# SCH_Senior_Transmitter_2026-04-14.net
KiCad netlist of a schematic drawn in EasyEDA
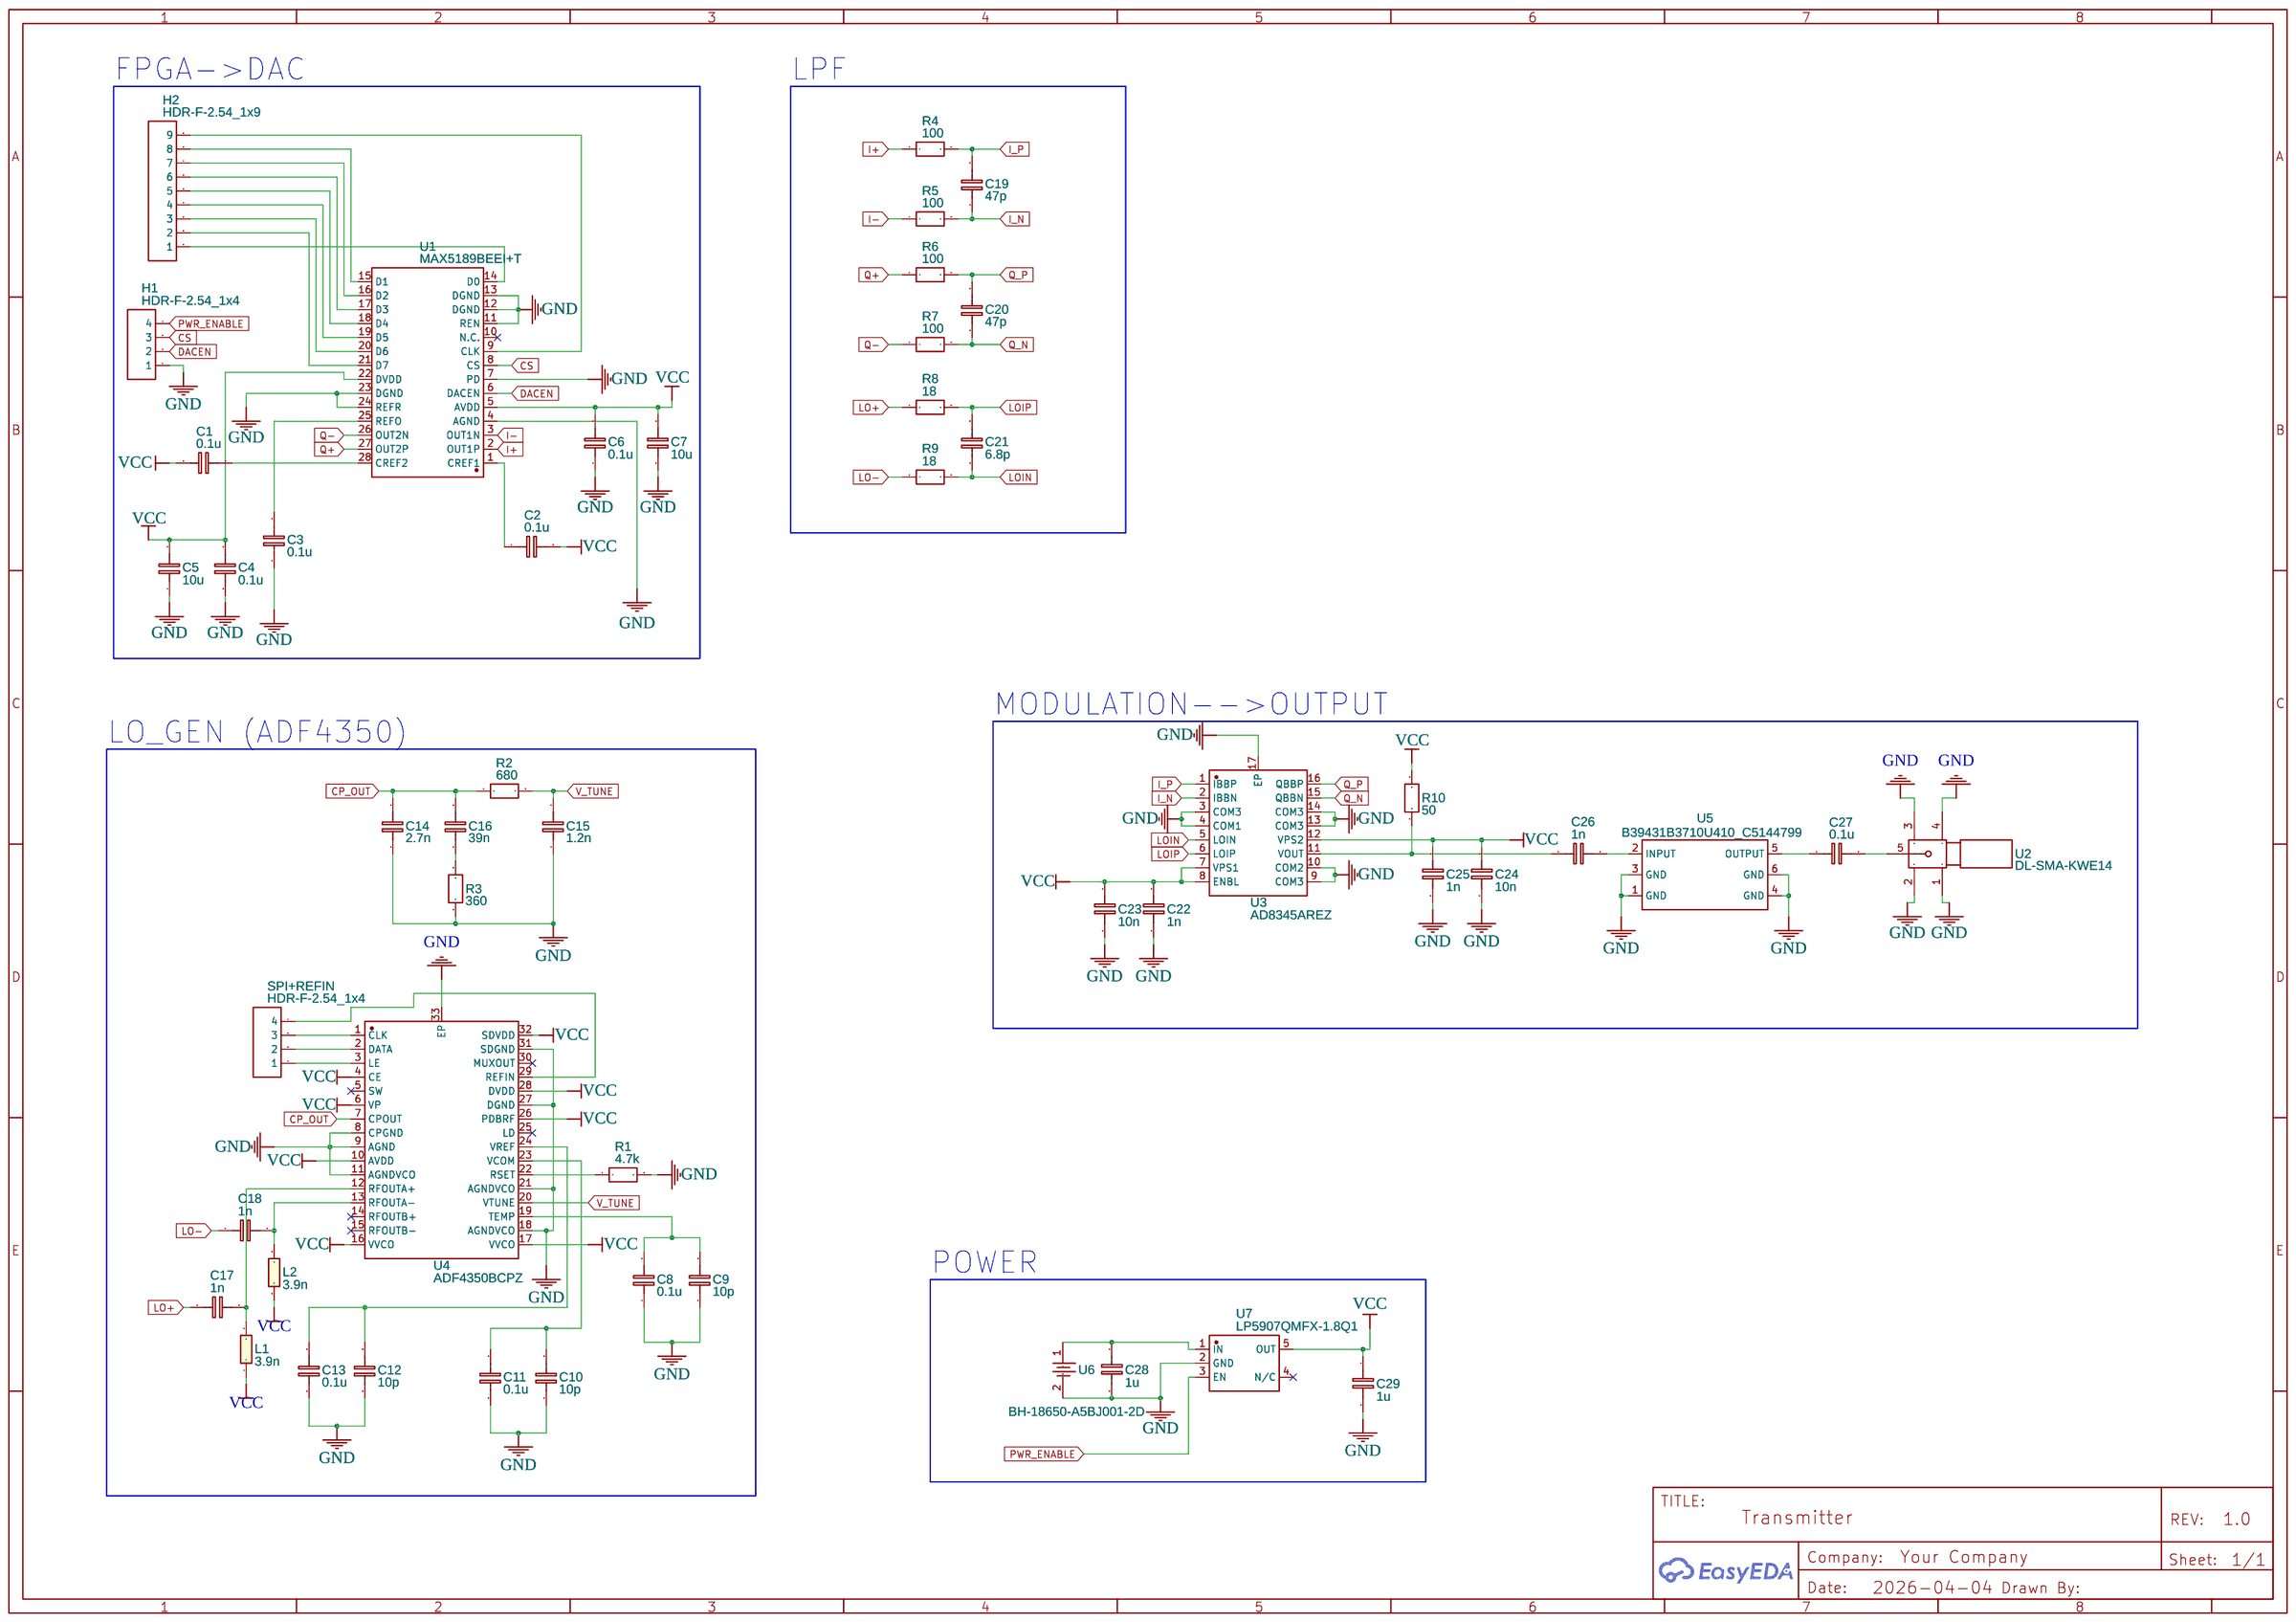
[diagram p0: schematic sheet]

(export (version "E")
  (design (tool "Eeschema 10.0.6"))
  (components
    (comp (ref "C1") (value "0.1u") (libsource (lib "") (part "C_0603_EU_6")))
    (comp (ref "C2") (value "0.1u") (libsource (lib "") (part "C_0603_EU_6")))
    (comp (ref "C3") (value "0.1u") (libsource (lib "") (part "C_0603_EU_2")))
    (comp (ref "C4") (value "0.1u") (libsource (lib "") (part "C_0603_EU_2")))
    (comp (ref "C5") (value "10u") (libsource (lib "") (part "C_0603_EU_2")))
    (comp (ref "C6") (value "0.1u") (libsource (lib "") (part "C_0603_EU_3")))
    (comp (ref "C7") (value "10u") (libsource (lib "") (part "C_0603_EU_3")))
    (comp (ref "C8") (value "0.1u") (libsource (lib "") (part "C_0603_EU_1")))
    (comp (ref "C9") (value "10p") (libsource (lib "") (part "C_0603_EU_1")))
    (comp (ref "C10") (value "10p") (libsource (lib "") (part "C_0603_EU_3")))
    (comp (ref "C11") (value "0.1u") (libsource (lib "") (part "C_0603_EU_3")))
    (comp (ref "C12") (value "10p") (libsource (lib "") (part "C_0603_EU_3")))
    (comp (ref "C13") (value "0.1u") (libsource (lib "") (part "C_0603_EU_2")))
    (comp (ref "C14") (value "2.7n") (libsource (lib "") (part "C_0603_EU_1")))
    (comp (ref "C15") (value "1.2n") (libsource (lib "") (part "C_0603_EU_1")))
    (comp (ref "C16") (value "39n") (libsource (lib "") (part "C_0603_EU_1")))
    (comp (ref "C17") (value "1n") (libsource (lib "") (part "C_0603_EU_6")))
    (comp (ref "C18") (value "1n") (libsource (lib "") (part "C_0603_EU_5")))
    (comp (ref "C19") (value "47p") (libsource (lib "") (part "C_0603_EU_2")))
    (comp (ref "C20") (value "47p") (libsource (lib "") (part "C_0603_EU_2")))
    (comp (ref "C21") (value "6.8p") (libsource (lib "") (part "C_0402_EU")))
    (comp (ref "C22") (value "1n") (libsource (lib "") (part "C_0603_EU")))
    (comp (ref "C23") (value "10n") (libsource (lib "") (part "C_0603_EU")))
    (comp (ref "C24") (value "10n") (libsource (lib "") (part "C_0603_EU")))
    (comp (ref "C25") (value "1n") (libsource (lib "") (part "C_0603_EU")))
    (comp (ref "C26") (value "1n") (libsource (lib "") (part "C_0603_EU_4")))
    (comp (ref "C27") (value "0.1u") (libsource (lib "") (part "C_0603_EU_4")))
    (comp (ref "C28") (value "1u") (libsource (lib "") (part "C_0603_EU_7")))
    (comp (ref "C29") (value "1u") (libsource (lib "") (part "C_0603_EU_7")))
    (comp (ref "H1") (value "HDR-F-2.54_1x4") (libsource (lib "") (part "HDR-F-2.54_1x4")))
    (comp (ref "H2") (value "HDR-F-2.54_1x9") (libsource (lib "") (part "HDR-F-2.54_1x9")))
    (comp (ref "L1") (value "3.9n") (libsource (lib "") (part "L0603_EU")))
    (comp (ref "L2") (value "3.9n") (libsource (lib "") (part "L0603_EU")))
    (comp (ref "R1") (value "4.7k") (libsource (lib "") (part "R_0603_EU")))
    (comp (ref "R2") (value "680") (libsource (lib "") (part "R_0603_EU")))
    (comp (ref "R3") (value "360") (libsource (lib "") (part "R_0603_EU_1")))
    (comp (ref "R4") (value "100") (libsource (lib "") (part "R_0603_EU")))
    (comp (ref "R5") (value "100") (libsource (lib "") (part "R_0603_EU")))
    (comp (ref "R6") (value "100") (libsource (lib "") (part "R_0603_EU")))
    (comp (ref "R7") (value "100") (libsource (lib "") (part "R_0603_EU")))
    (comp (ref "R8") (value "18") (libsource (lib "") (part "R_0402_EU")))
    (comp (ref "R9") (value "18") (libsource (lib "") (part "R_0402_EU")))
    (comp (ref "R10") (value "50") (libsource (lib "") (part "R_0603_EU_1")))
    (comp (ref "SPI+REFIN") (value "HDR-F-2.54_1x4") (libsource (lib "") (part "HDR-F-2.54_1x4_1")))
    (comp (ref "U1")
      (value "MAX5189BEEI+T")
      (fields (field (name "Manufacturer") "ADI(亚德诺)/MAXIM(美信)"))
      (libsource (lib "") (part "MAX5189BEEI+T"))
    )
    (comp (ref "U2")
      (value "DL-SMA-KWE14")
      (fields (field (name "Manufacturer") "DEALON(德艺隆)"))
      (libsource (lib "") (part "DL-SMA-KWE14"))
    )
    (comp (ref "U3")
      (value "AD8345AREZ")
      (fields (field (name "Manufacturer") "ADI(亚德诺)"))
      (libsource (lib "") (part "AD8345AREZ"))
    )
    (comp (ref "U4")
      (value "ADF4350BCPZ")
      (fields (field (name "Manufacturer") "ADI(亚德诺)"))
      (libsource (lib "") (part "ADF4350BCPZ"))
    )
    (comp (ref "U5")
      (value "B39431B3710U410_C5144799")
      (fields (field (name "Manufacturer Part") "B39431B3710U410"))
      (libsource (lib "") (part "B39431B3710U410_C5144799"))
    )
    (comp (ref "U6")
      (value "BH-18650-A5BJ001-2D")
      (fields (field (name "Manufacturer") "MYOUNG(美阳)"))
      (libsource (lib "") (part "BH-18650-A5BJ001-2D"))
    )
    (comp (ref "U7")
      (value "LP5907QMFX-1.8Q1")
      (fields (field (name "Manufacturer") "TI(德州仪器)"))
      (libsource (lib "") (part "LP5907QMFX-1.8Q1"))
    )
  )
  (nets
    (net (code "1") (name "CP_OUT") (class "Default")
      (node (ref "C14") (pin "2") (pinfunction "2_2") (pintype "unspecified"))
      (node (ref "C16") (pin "2") (pinfunction "2_2") (pintype "unspecified"))
      (node (ref "R2") (pin "1") (pinfunction "1_1") (pintype "unspecified"))
      (node (ref "U4") (pin "7") (pinfunction "CPOUT_7") (pintype "unspecified"))
    )
    (net (code "2") (name "CS") (class "Default")
      (node (ref "H1") (pin "3") (pinfunction "3_3") (pintype "unspecified"))
      (node (ref "U1") (pin "8") (pinfunction "CS_8") (pintype "unspecified"))
    )
    (net (code "3") (name "DACEN") (class "Default")
      (node (ref "H1") (pin "2") (pinfunction "2_2") (pintype "unspecified"))
      (node (ref "U1") (pin "6") (pinfunction "DACEN_6") (pintype "unspecified"))
    )
    (net (code "4") (name "GND") (class "Default")
      (node (ref "C10") (pin "1") (pinfunction "1_1") (pintype "unspecified"))
      (node (ref "C11") (pin "1") (pinfunction "1_1") (pintype "unspecified"))
      (node (ref "C12") (pin "1") (pinfunction "1_1") (pintype "unspecified"))
      (node (ref "C13") (pin "1") (pinfunction "1_1") (pintype "unspecified"))
      (node (ref "C14") (pin "1") (pinfunction "1_1") (pintype "unspecified"))
      (node (ref "C15") (pin "1") (pinfunction "1_1") (pintype "unspecified"))
      (node (ref "C22") (pin "2") (pinfunction "2_2") (pintype "unspecified"))
      (node (ref "C23") (pin "2") (pinfunction "2_2") (pintype "unspecified"))
      (node (ref "C24") (pin "2") (pinfunction "2_2") (pintype "unspecified"))
      (node (ref "C25") (pin "2") (pinfunction "2_2") (pintype "unspecified"))
      (node (ref "C28") (pin "2") (pinfunction "2_2") (pintype "unspecified"))
      (node (ref "C29") (pin "2") (pinfunction "2_2") (pintype "unspecified"))
      (node (ref "C3") (pin "1") (pinfunction "1_1") (pintype "unspecified"))
      (node (ref "C4") (pin "1") (pinfunction "1_1") (pintype "unspecified"))
      (node (ref "C5") (pin "1") (pinfunction "1_1") (pintype "unspecified"))
      (node (ref "C6") (pin "1") (pinfunction "1_1") (pintype "unspecified"))
      (node (ref "C7") (pin "1") (pinfunction "1_1") (pintype "unspecified"))
      (node (ref "C8") (pin "1") (pinfunction "1_1") (pintype "unspecified"))
      (node (ref "C9") (pin "1") (pinfunction "1_1") (pintype "unspecified"))
      (node (ref "H1") (pin "1") (pinfunction "1_1") (pintype "unspecified"))
      (node (ref "R1") (pin "2") (pinfunction "2_2") (pintype "unspecified"))
      (node (ref "R3") (pin "1") (pinfunction "1_1") (pintype "unspecified"))
      (node (ref "U1") (pin "11") (pinfunction "REN_11") (pintype "unspecified"))
      (node (ref "U1") (pin "12") (pinfunction "DGND_12") (pintype "unspecified"))
      (node (ref "U1") (pin "13") (pinfunction "DGND_13") (pintype "unspecified"))
      (node (ref "U1") (pin "23") (pinfunction "DGND_23") (pintype "unspecified"))
      (node (ref "U1") (pin "24") (pinfunction "REFR_24") (pintype "unspecified"))
      (node (ref "U1") (pin "4") (pinfunction "AGND_4") (pintype "unspecified"))
      (node (ref "U1") (pin "7") (pinfunction "PD_7") (pintype "unspecified"))
      (node (ref "U2") (pin "1") (pinfunction "1_1") (pintype "unspecified"))
      (node (ref "U2") (pin "2") (pinfunction "2_2") (pintype "unspecified"))
      (node (ref "U2") (pin "3") (pinfunction "3_3") (pintype "unspecified"))
      (node (ref "U2") (pin "4") (pinfunction "4_4") (pintype "unspecified"))
      (node (ref "U3") (pin "10") (pinfunction "COM2_10") (pintype "unspecified"))
      (node (ref "U3") (pin "13") (pinfunction "COM3_13") (pintype "unspecified"))
      (node (ref "U3") (pin "14") (pinfunction "COM3_14") (pintype "unspecified"))
      (node (ref "U3") (pin "17") (pinfunction "EP_17") (pintype "unspecified"))
      (node (ref "U3") (pin "3") (pinfunction "COM3_3") (pintype "unspecified"))
      (node (ref "U3") (pin "4") (pinfunction "COM1_4") (pintype "unspecified"))
      (node (ref "U3") (pin "9") (pinfunction "COM3_9") (pintype "unspecified"))
      (node (ref "U4") (pin "11") (pinfunction "AGNDVCO_11") (pintype "unspecified"))
      (node (ref "U4") (pin "18") (pinfunction "AGNDVCO_18") (pintype "unspecified"))
      (node (ref "U4") (pin "21") (pinfunction "AGNDVCO_21") (pintype "unspecified"))
      (node (ref "U4") (pin "27") (pinfunction "DGND_27") (pintype "unspecified"))
      (node (ref "U4") (pin "31") (pinfunction "SDGND_31") (pintype "unspecified"))
      (node (ref "U4") (pin "33") (pinfunction "EP_33") (pintype "unspecified"))
      (node (ref "U4") (pin "8") (pinfunction "CPGND_8") (pintype "unspecified"))
      (node (ref "U4") (pin "9") (pinfunction "AGND_9") (pintype "unspecified"))
      (node (ref "U5") (pin "1") (pinfunction "GND_1") (pintype "unspecified"))
      (node (ref "U5") (pin "3") (pinfunction "GND_3") (pintype "unspecified"))
      (node (ref "U5") (pin "4") (pinfunction "GND_4") (pintype "unspecified"))
      (node (ref "U5") (pin "6") (pinfunction "GND_6") (pintype "unspecified"))
      (node (ref "U6") (pin "2") (pinfunction "2_2") (pintype "input"))
      (node (ref "U7") (pin "2") (pinfunction "GND_2") (pintype "unspecified"))
    )
    (net (code "5") (name "I+") (class "Default")
      (node (ref "R4") (pin "1") (pinfunction "1_1") (pintype "unspecified"))
      (node (ref "U1") (pin "2") (pinfunction "OUT1P_2") (pintype "unspecified"))
    )
    (net (code "6") (name "I-") (class "Default")
      (node (ref "R5") (pin "1") (pinfunction "1_1") (pintype "unspecified"))
      (node (ref "U1") (pin "3") (pinfunction "OUT1N_3") (pintype "unspecified"))
    )
    (net (code "7") (name "I_N") (class "Default")
      (node (ref "C19") (pin "1") (pinfunction "1_1") (pintype "unspecified"))
      (node (ref "R5") (pin "2") (pinfunction "2_2") (pintype "unspecified"))
      (node (ref "U3") (pin "2") (pinfunction "IBBN_2") (pintype "unspecified"))
    )
    (net (code "8") (name "I_P") (class "Default")
      (node (ref "C19") (pin "2") (pinfunction "2_2") (pintype "unspecified"))
      (node (ref "R4") (pin "2") (pinfunction "2_2") (pintype "unspecified"))
      (node (ref "U3") (pin "1") (pinfunction "IBBP_1") (pintype "unspecified"))
    )
    (net (code "9") (name "LO+") (class "Default")
      (node (ref "C17") (pin "1") (pinfunction "1_1") (pintype "unspecified"))
      (node (ref "R8") (pin "1") (pinfunction "1_1") (pintype "unspecified"))
    )
    (net (code "10") (name "LO-") (class "Default")
      (node (ref "C18") (pin "1") (pinfunction "1_1") (pintype "unspecified"))
      (node (ref "R9") (pin "1") (pinfunction "1_1") (pintype "unspecified"))
    )
    (net (code "11") (name "LOIN") (class "Default")
      (node (ref "C21") (pin "1") (pinfunction "1_1") (pintype "unspecified"))
      (node (ref "R9") (pin "2") (pinfunction "2_2") (pintype "unspecified"))
      (node (ref "U3") (pin "5") (pinfunction "LOIN_5") (pintype "unspecified"))
    )
    (net (code "12") (name "LOIP") (class "Default")
      (node (ref "C21") (pin "2") (pinfunction "2_2") (pintype "unspecified"))
      (node (ref "R8") (pin "2") (pinfunction "2_2") (pintype "unspecified"))
      (node (ref "U3") (pin "6") (pinfunction "LOIP_6") (pintype "unspecified"))
    )
    (net (code "13") (name "Net-(C16-Pad1)") (class "Default")
      (node (ref "C16") (pin "1") (pinfunction "1_1") (pintype "unspecified"))
      (node (ref "R3") (pin "2") (pinfunction "2_2") (pintype "unspecified"))
    )
    (net (code "14") (name "Net-(C27-Pad2)") (class "Default")
      (node (ref "C27") (pin "2") (pinfunction "2_2") (pintype "unspecified"))
      (node (ref "U2") (pin "5") (pinfunction "5_5") (pintype "unspecified"))
    )
    (net (code "15") (name "Net-(U1-CLK)") (class "Default")
      (node (ref "H2") (pin "9") (pinfunction "9_9") (pintype "unspecified"))
      (node (ref "U1") (pin "9") (pinfunction "CLK_9") (pintype "unspecified"))
    )
    (net (code "16") (name "Net-(U1-CREF1)") (class "Default")
      (node (ref "C2") (pin "1") (pinfunction "1_1") (pintype "unspecified"))
      (node (ref "U1") (pin "1") (pinfunction "CREF1_1") (pintype "unspecified"))
    )
    (net (code "17") (name "Net-(U1-CREF2)") (class "Default")
      (node (ref "C1") (pin "2") (pinfunction "2_2") (pintype "unspecified"))
      (node (ref "U1") (pin "28") (pinfunction "CREF2_28") (pintype "unspecified"))
    )
    (net (code "18") (name "Net-(U1-D0)") (class "Default")
      (node (ref "H2") (pin "1") (pinfunction "1_1") (pintype "unspecified"))
      (node (ref "U1") (pin "14") (pinfunction "D0_14") (pintype "unspecified"))
    )
    (net (code "19") (name "Net-(U1-D1)") (class "Default")
      (node (ref "H2") (pin "8") (pinfunction "8_8") (pintype "unspecified"))
      (node (ref "U1") (pin "15") (pinfunction "D1_15") (pintype "unspecified"))
    )
    (net (code "20") (name "Net-(U1-D2)") (class "Default")
      (node (ref "H2") (pin "7") (pinfunction "7_7") (pintype "unspecified"))
      (node (ref "U1") (pin "16") (pinfunction "D2_16") (pintype "unspecified"))
    )
    (net (code "21") (name "Net-(U1-D3)") (class "Default")
      (node (ref "H2") (pin "6") (pinfunction "6_6") (pintype "unspecified"))
      (node (ref "U1") (pin "17") (pinfunction "D3_17") (pintype "unspecified"))
    )
    (net (code "22") (name "Net-(U1-D4)") (class "Default")
      (node (ref "H2") (pin "5") (pinfunction "5_5") (pintype "unspecified"))
      (node (ref "U1") (pin "18") (pinfunction "D4_18") (pintype "unspecified"))
    )
    (net (code "23") (name "Net-(U1-D5)") (class "Default")
      (node (ref "H2") (pin "4") (pinfunction "4_4") (pintype "unspecified"))
      (node (ref "U1") (pin "19") (pinfunction "D5_19") (pintype "unspecified"))
    )
    (net (code "24") (name "Net-(U1-D6)") (class "Default")
      (node (ref "H2") (pin "3") (pinfunction "3_3") (pintype "unspecified"))
      (node (ref "U1") (pin "20") (pinfunction "D6_20") (pintype "unspecified"))
    )
    (net (code "25") (name "Net-(U1-D7)") (class "Default")
      (node (ref "H2") (pin "2") (pinfunction "2_2") (pintype "unspecified"))
      (node (ref "U1") (pin "21") (pinfunction "D7_21") (pintype "unspecified"))
    )
    (net (code "26") (name "Net-(U1-REFO)") (class "Default")
      (node (ref "C3") (pin "2") (pinfunction "2_2") (pintype "unspecified"))
      (node (ref "U1") (pin "25") (pinfunction "REFO_25") (pintype "unspecified"))
    )
    (net (code "27") (name "Net-(U3-VOUT)") (class "Default")
      (node (ref "C26") (pin "1") (pinfunction "1_1") (pintype "unspecified"))
      (node (ref "R10") (pin "1") (pinfunction "1_1") (pintype "unspecified"))
      (node (ref "U3") (pin "11") (pinfunction "VOUT_11") (pintype "unspecified"))
    )
    (net (code "28") (name "Net-(U4-CLK)") (class "Default")
      (node (ref "SPI+REFIN") (pin "3") (pinfunction "3_3") (pintype "unspecified"))
      (node (ref "U4") (pin "1") (pinfunction "CLK_1") (pintype "unspecified"))
    )
    (net (code "29") (name "Net-(U4-DATA)") (class "Default")
      (node (ref "SPI+REFIN") (pin "2") (pinfunction "2_2") (pintype "unspecified"))
      (node (ref "U4") (pin "2") (pinfunction "DATA_2") (pintype "unspecified"))
    )
    (net (code "30") (name "Net-(U4-LE)") (class "Default")
      (node (ref "SPI+REFIN") (pin "1") (pinfunction "1_1") (pintype "unspecified"))
      (node (ref "U4") (pin "3") (pinfunction "LE_3") (pintype "unspecified"))
    )
    (net (code "31") (name "Net-(U4-REFIN)") (class "Default")
      (node (ref "SPI+REFIN") (pin "4") (pinfunction "4_4") (pintype "unspecified"))
      (node (ref "U4") (pin "29") (pinfunction "REFIN_29") (pintype "unspecified"))
    )
    (net (code "32") (name "Net-(U4-RFOUTA+)") (class "Default")
      (node (ref "C17") (pin "2") (pinfunction "2_2") (pintype "unspecified"))
      (node (ref "L1") (pin "2") (pinfunction "2_2") (pintype "unspecified"))
      (node (ref "U4") (pin "12") (pinfunction "RFOUTA+_12") (pintype "unspecified"))
    )
    (net (code "33") (name "Net-(U4-RFOUTA-)") (class "Default")
      (node (ref "C18") (pin "2") (pinfunction "2_2") (pintype "unspecified"))
      (node (ref "L2") (pin "2") (pinfunction "2_2") (pintype "unspecified"))
      (node (ref "U4") (pin "13") (pinfunction "RFOUTA-_13") (pintype "unspecified"))
    )
    (net (code "34") (name "Net-(U4-RSET)") (class "Default")
      (node (ref "R1") (pin "1") (pinfunction "1_1") (pintype "unspecified"))
      (node (ref "U4") (pin "22") (pinfunction "RSET_22") (pintype "unspecified"))
    )
    (net (code "35") (name "Net-(U4-TEMP)") (class "Default")
      (node (ref "C8") (pin "2") (pinfunction "2_2") (pintype "unspecified"))
      (node (ref "C9") (pin "2") (pinfunction "2_2") (pintype "unspecified"))
      (node (ref "U4") (pin "19") (pinfunction "TEMP_19") (pintype "unspecified"))
    )
    (net (code "36") (name "Net-(U4-VCOM)") (class "Default")
      (node (ref "C10") (pin "2") (pinfunction "2_2") (pintype "unspecified"))
      (node (ref "C11") (pin "2") (pinfunction "2_2") (pintype "unspecified"))
      (node (ref "U4") (pin "23") (pinfunction "VCOM_23") (pintype "unspecified"))
    )
    (net (code "37") (name "Net-(U4-VREF)") (class "Default")
      (node (ref "C12") (pin "2") (pinfunction "2_2") (pintype "unspecified"))
      (node (ref "C13") (pin "2") (pinfunction "2_2") (pintype "unspecified"))
      (node (ref "U4") (pin "24") (pinfunction "VREF_24") (pintype "unspecified"))
    )
    (net (code "38") (name "Net-(U5-INPUT)") (class "Default")
      (node (ref "C26") (pin "2") (pinfunction "2_2") (pintype "unspecified"))
      (node (ref "U5") (pin "2") (pinfunction "INPUT_2") (pintype "unspecified"))
    )
    (net (code "39") (name "Net-(U5-OUTPUT)") (class "Default")
      (node (ref "C27") (pin "1") (pinfunction "1_1") (pintype "unspecified"))
      (node (ref "U5") (pin "5") (pinfunction "OUTPUT_5") (pintype "unspecified"))
    )
    (net (code "40") (name "Net-(U7-IN)") (class "Default")
      (node (ref "C28") (pin "1") (pinfunction "1_1") (pintype "unspecified"))
      (node (ref "U6") (pin "1") (pinfunction "1_1") (pintype "input"))
      (node (ref "U7") (pin "1") (pinfunction "IN_1") (pintype "unspecified"))
    )
    (net (code "41") (name "PWR_ENABLE") (class "Default")
      (node (ref "H1") (pin "4") (pinfunction "4_4") (pintype "unspecified"))
      (node (ref "U7") (pin "3") (pinfunction "EN_3") (pintype "unspecified"))
    )
    (net (code "42") (name "Q+") (class "Default")
      (node (ref "R6") (pin "1") (pinfunction "1_1") (pintype "unspecified"))
      (node (ref "U1") (pin "27") (pinfunction "OUT2P_27") (pintype "unspecified"))
    )
    (net (code "43") (name "Q-") (class "Default")
      (node (ref "R7") (pin "1") (pinfunction "1_1") (pintype "unspecified"))
      (node (ref "U1") (pin "26") (pinfunction "OUT2N_26") (pintype "unspecified"))
    )
    (net (code "44") (name "Q_N") (class "Default")
      (node (ref "C20") (pin "1") (pinfunction "1_1") (pintype "unspecified"))
      (node (ref "R7") (pin "2") (pinfunction "2_2") (pintype "unspecified"))
      (node (ref "U3") (pin "15") (pinfunction "QBBN_15") (pintype "unspecified"))
    )
    (net (code "45") (name "Q_P") (class "Default")
      (node (ref "C20") (pin "2") (pinfunction "2_2") (pintype "unspecified"))
      (node (ref "R6") (pin "2") (pinfunction "2_2") (pintype "unspecified"))
      (node (ref "U3") (pin "16") (pinfunction "QBBP_16") (pintype "unspecified"))
    )
    (net (code "46") (name "VCC") (class "Default")
      (node (ref "C1") (pin "1") (pinfunction "1_1") (pintype "unspecified"))
      (node (ref "C2") (pin "2") (pinfunction "2_2") (pintype "unspecified"))
      (node (ref "C22") (pin "1") (pinfunction "1_1") (pintype "unspecified"))
      (node (ref "C23") (pin "1") (pinfunction "1_1") (pintype "unspecified"))
      (node (ref "C24") (pin "1") (pinfunction "1_1") (pintype "unspecified"))
      (node (ref "C25") (pin "1") (pinfunction "1_1") (pintype "unspecified"))
      (node (ref "C29") (pin "1") (pinfunction "1_1") (pintype "unspecified"))
      (node (ref "C4") (pin "2") (pinfunction "2_2") (pintype "unspecified"))
      (node (ref "C5") (pin "2") (pinfunction "2_2") (pintype "unspecified"))
      (node (ref "C6") (pin "2") (pinfunction "2_2") (pintype "unspecified"))
      (node (ref "C7") (pin "2") (pinfunction "2_2") (pintype "unspecified"))
      (node (ref "L1") (pin "1") (pinfunction "1_1") (pintype "unspecified"))
      (node (ref "L2") (pin "1") (pinfunction "1_1") (pintype "unspecified"))
      (node (ref "R10") (pin "2") (pinfunction "2_2") (pintype "unspecified"))
      (node (ref "U1") (pin "22") (pinfunction "DVDD_22") (pintype "unspecified"))
      (node (ref "U1") (pin "5") (pinfunction "AVDD_5") (pintype "unspecified"))
      (node (ref "U3") (pin "12") (pinfunction "VPS2_12") (pintype "unspecified"))
      (node (ref "U3") (pin "7") (pinfunction "VPS1_7") (pintype "unspecified"))
      (node (ref "U3") (pin "8") (pinfunction "ENBL_8") (pintype "unspecified"))
      (node (ref "U4") (pin "10") (pinfunction "AVDD_10") (pintype "unspecified"))
      (node (ref "U4") (pin "16") (pinfunction "VVCO_16") (pintype "unspecified"))
      (node (ref "U4") (pin "17") (pinfunction "VVCO_17") (pintype "unspecified"))
      (node (ref "U4") (pin "26") (pinfunction "PDBRF_26") (pintype "unspecified"))
      (node (ref "U4") (pin "28") (pinfunction "DVDD_28") (pintype "unspecified"))
      (node (ref "U4") (pin "32") (pinfunction "SDVDD_32") (pintype "unspecified"))
      (node (ref "U4") (pin "4") (pinfunction "CE_4") (pintype "unspecified"))
      (node (ref "U4") (pin "6") (pinfunction "VP_6") (pintype "unspecified"))
      (node (ref "U7") (pin "5") (pinfunction "OUT_5") (pintype "unspecified"))
    )
    (net (code "47") (name "V_TUNE") (class "Default")
      (node (ref "C15") (pin "2") (pinfunction "2_2") (pintype "unspecified"))
      (node (ref "R2") (pin "2") (pinfunction "2_2") (pintype "unspecified"))
      (node (ref "U4") (pin "20") (pinfunction "VTUNE_20") (pintype "unspecified"))
    )
    (net (code "48") (name "unconnected-(U1-N.C.-Pad10)") (class "Default")
      (node (ref "U1") (pin "10") (pinfunction "N.C._10") (pintype "unspecified+no_connect"))
    )
    (net (code "49") (name "unconnected-(U4-LD-Pad25)") (class "Default")
      (node (ref "U4") (pin "25") (pinfunction "LD_25") (pintype "unspecified+no_connect"))
    )
    (net (code "50") (name "unconnected-(U4-MUXOUT-Pad30)") (class "Default")
      (node (ref "U4") (pin "30") (pinfunction "MUXOUT_30") (pintype "unspecified+no_connect"))
    )
    (net (code "51") (name "unconnected-(U4-RFOUTB+-Pad14)") (class "Default")
      (node (ref "U4") (pin "14") (pinfunction "RFOUTB+_14") (pintype "unspecified+no_connect"))
    )
    (net (code "52") (name "unconnected-(U4-RFOUTB--Pad15)") (class "Default")
      (node (ref "U4") (pin "15") (pinfunction "RFOUTB-_15") (pintype "unspecified+no_connect"))
    )
    (net (code "53") (name "unconnected-(U4-SW-Pad5)") (class "Default")
      (node (ref "U4") (pin "5") (pinfunction "SW_5") (pintype "unspecified+no_connect"))
    )
    (net (code "54") (name "unconnected-(U7-N{slash}C-Pad4)") (class "Default")
      (node (ref "U7") (pin "4") (pinfunction "N/C_4") (pintype "unspecified+no_connect"))
    )
  )
)
